# ATtiny85_Board.net
KiCad netlist of a schematic drawn in EAGLE
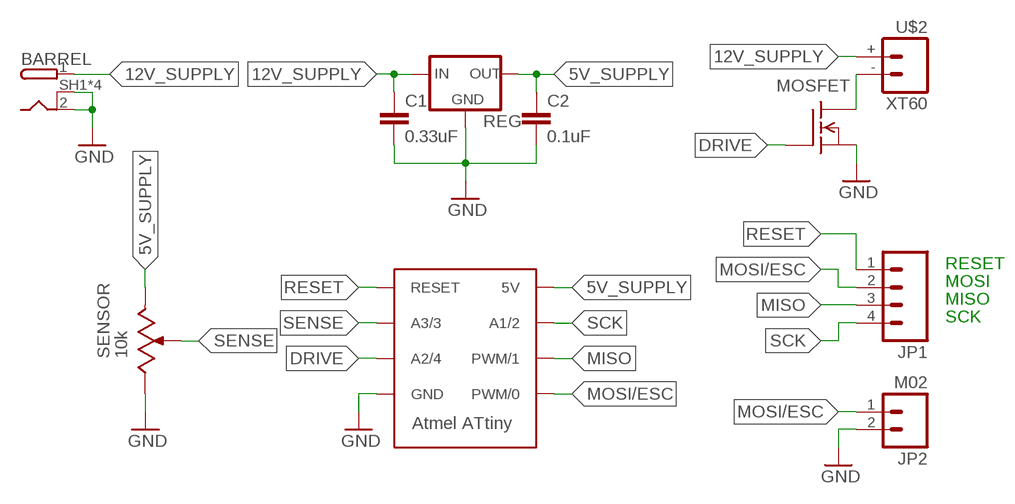
[diagram p0: schematic, sheet 1]

(export (version "E")
  (design (tool "Eeschema 10.0.6"))
  (components
    (comp (ref "BARREL")
      (value "PJ-082BH")
      (footprint "eagle-import:PJ-082BH")
      (libsource (lib "eagle-import") (part "PJ-082BH"))
    )
    (comp (ref "C1")
      (value "0.33uF")
      (footprint "eagle-import:0805")
      (libsource (lib "eagle-import") (part "CAP0805"))
    )
    (comp (ref "C2")
      (value "0.1uF")
      (footprint "eagle-import:0805")
      (libsource (lib "eagle-import") (part "CAP0805"))
    )
    (comp (ref "JP1")
      (value "M04")
      (footprint "eagle-import:1X04")
      (libsource (lib "eagle-import") (part "M04"))
    )
    (comp (ref "JP2")
      (value "M02")
      (footprint "eagle-import:1X02")
      (libsource (lib "eagle-import") (part "M02"))
    )
    (comp (ref "MOSFET")
      (value "SI2312")
      (footprint "eagle-import:SOT-23")
      (libsource (lib "eagle-import") (part "SI2312"))
    )
    (comp (ref "REG")
      (value "L78L")
      (footprint "eagle-import:SOT-89")
      (libsource (lib "eagle-import") (part "L78L"))
    )
    (comp (ref "SENSOR")
      (value "10k")
      (footprint "eagle-import:SV03A")
      (libsource (lib "eagle-import") (part "SV03"))
    )
    (comp (ref "U$1")
      (value "ATTINY")
      (footprint "eagle-import:8S2")
      (libsource (lib "eagle-import") (part "ATTINY"))
    )
    (comp (ref "U$2")
      (value "XT60")
      (footprint "eagle-import:XT60")
      (libsource (lib "eagle-import") (part "XT60"))
    )
  )
  (nets
    (net (code "1") (name "5V_SUPPLY") (class "Default")
      (node (ref "C2") (pin "1") (pinfunction "1_1") (pintype "passive"))
      (node (ref "REG") (pin "1") (pinfunction "OUT_1") (pintype "output"))
      (node (ref "SENSOR") (pin "1") (pinfunction "E_1") (pintype "passive"))
      (node (ref "U$1") (pin "8") (pinfunction "5V_8") (pintype "bidirectional"))
    )
    (net (code "2") (name "12V_SUPPLY") (class "Default")
      (node (ref "BARREL") (pin "1") (pinfunction "PWR_1") (pintype "power_in"))
      (node (ref "C1") (pin "1") (pinfunction "1_1") (pintype "passive"))
      (node (ref "REG") (pin "3") (pinfunction "IN_3") (pintype "input"))
      (node (ref "U$2") (pin "+") (pinfunction "2_+") (pintype "passive"))
    )
    (net (code "3") (name "DRIVE") (class "Default")
      (node (ref "MOSFET") (pin "1") (pinfunction "G_1") (pintype "passive"))
      (node (ref "U$1") (pin "3") (pinfunction "A2/4_3") (pintype "bidirectional"))
    )
    (net (code "4") (name "GND") (class "Default")
      (node (ref "BARREL") (pin "2") (pinfunction "GND_2") (pintype "power_in"))
      (node (ref "BARREL") (pin "SH1") (pinfunction "SHIELD_SH1") (pintype "power_in"))
      (node (ref "BARREL") (pin "SH2") (pinfunction "SHIELD_SH2") (pintype "power_in"))
      (node (ref "BARREL") (pin "SH3") (pinfunction "SHIELD_SH3") (pintype "power_in"))
      (node (ref "BARREL") (pin "SH4") (pinfunction "SHIELD_SH4") (pintype "power_in"))
      (node (ref "C1") (pin "2") (pinfunction "2_2") (pintype "passive"))
      (node (ref "C2") (pin "2") (pinfunction "2_2") (pintype "passive"))
      (node (ref "JP2") (pin "2") (pinfunction "2_2") (pintype "passive"))
      (node (ref "MOSFET") (pin "2") (pinfunction "S_2") (pintype "passive"))
      (node (ref "REG") (pin "2") (pinfunction "GND_2") (pintype "input"))
      (node (ref "REG") (pin "2.1") (pinfunction "GND_2.1") (pintype "input"))
      (node (ref "REG") (pin "2.2") (pinfunction "GND_2.2") (pintype "input"))
      (node (ref "SENSOR") (pin "3") (pinfunction "A_3") (pintype "passive"))
      (node (ref "U$1") (pin "4") (pinfunction "GND_4") (pintype "bidirectional"))
    )
    (net (code "5") (name "MISO") (class "Default")
      (node (ref "JP1") (pin "3") (pinfunction "3_3") (pintype "passive"))
      (node (ref "U$1") (pin "6") (pinfunction "PWM/1_6") (pintype "bidirectional"))
    )
    (net (code "6") (name "MOSI{slash}ESC") (class "Default")
      (node (ref "JP1") (pin "2") (pinfunction "2_2") (pintype "passive"))
      (node (ref "JP2") (pin "1") (pinfunction "1_1") (pintype "passive"))
      (node (ref "U$1") (pin "5") (pinfunction "PWM/0_5") (pintype "bidirectional"))
    )
    (net (code "7") (name "Net-(MOSFET-D)") (class "Default")
      (node (ref "MOSFET") (pin "3") (pinfunction "D_3") (pintype "passive"))
      (node (ref "U$2") (pin "-") (pinfunction "1_-") (pintype "passive"))
    )
    (net (code "8") (name "RESET") (class "Default")
      (node (ref "JP1") (pin "1") (pinfunction "1_1") (pintype "passive"))
      (node (ref "U$1") (pin "1") (pinfunction "RESET_1") (pintype "bidirectional"))
    )
    (net (code "9") (name "SCK") (class "Default")
      (node (ref "JP1") (pin "4") (pinfunction "4_4") (pintype "passive"))
      (node (ref "U$1") (pin "7") (pinfunction "A1/2_7") (pintype "bidirectional"))
    )
    (net (code "10") (name "SENSE") (class "Default")
      (node (ref "SENSOR") (pin "2") (pinfunction "S_2") (pintype "passive"))
      (node (ref "SENSOR") (pin "2.1") (pinfunction "S_2.1") (pintype "passive"))
      (node (ref "U$1") (pin "2") (pinfunction "A3/3_2") (pintype "bidirectional"))
    )
  )
)
